# optoreflector.net
KiCad netlist of a schematic drawn in EAGLE
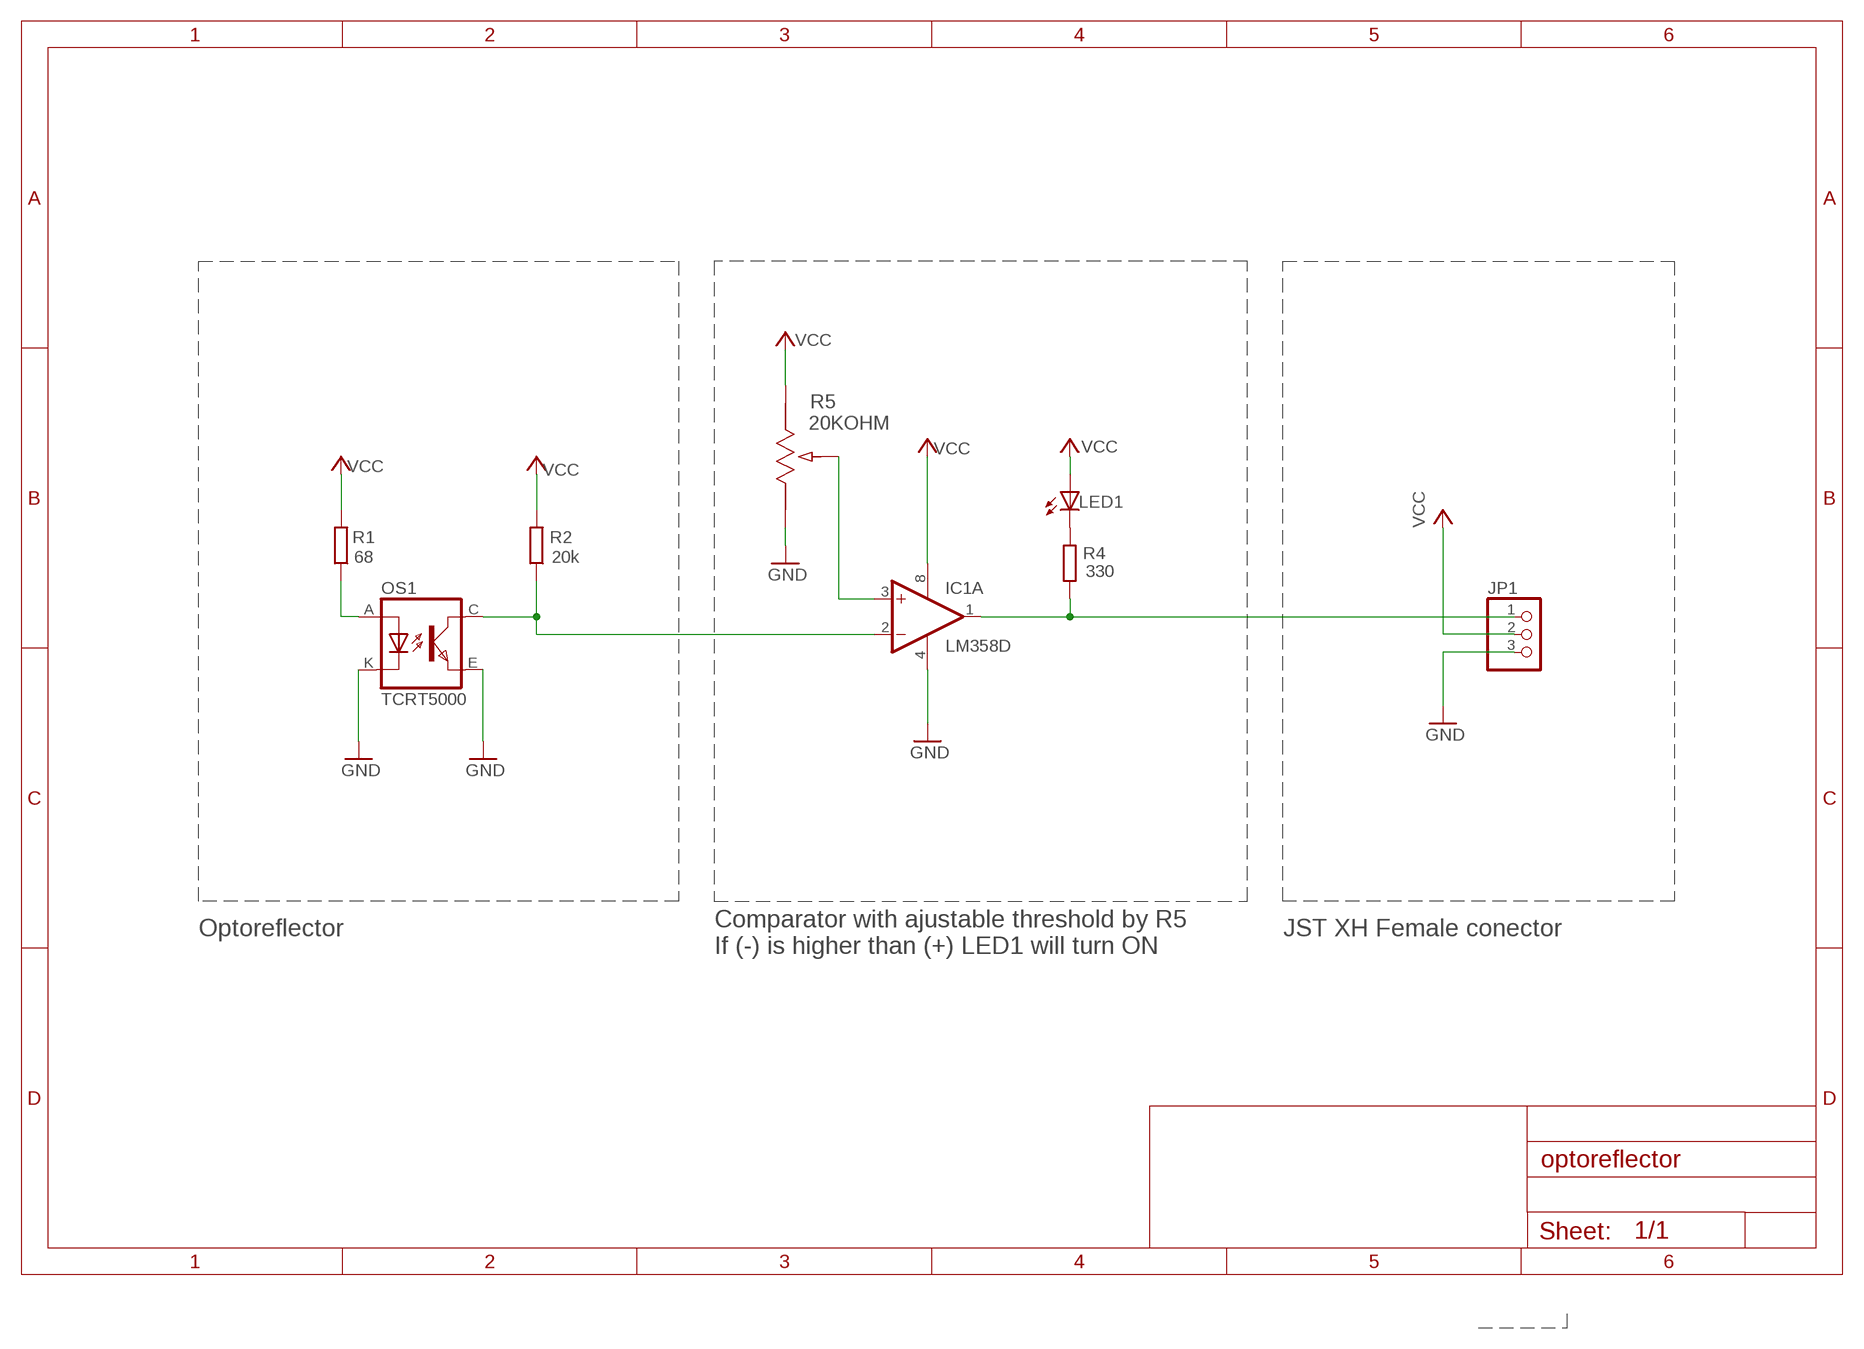
[diagram p0: schematic, sheet 1]

(export (version "E")
  (design (tool "Eeschema 10.0.6"))
  (components
    (comp (ref "IC1")
      (value "LM358D")
      (footprint "eagle-import:SO08")
      (libsource (lib "eagle-import") (part "LM358D"))
    )
    (comp (ref "JP1")
      (value "PINHD-1X3")
      (footprint "eagle-import:1X03")
      (libsource (lib "eagle-import") (part "PINHD-1X3"))
    )
    (comp (ref "LED1")
      (value "LEDCHIP-LED0805")
      (footprint "eagle-import:CHIP-LED0805")
      (libsource (lib "eagle-import") (part "LEDCHIP-LED0805"))
    )
    (comp (ref "OS1")
      (value "TCRT5000")
      (footprint "eagle-import:TCRT5000")
      (libsource (lib "eagle-import") (part "TCRT5000"))
    )
    (comp (ref "R1")
      (value "68")
      (footprint "eagle-import:R0805")
      (libsource (lib "eagle-import") (part "R-EU_R0805"))
    )
    (comp (ref "R2")
      (value "20k")
      (footprint "eagle-import:R0805")
      (libsource (lib "eagle-import") (part "R-EU_R0805"))
    )
    (comp (ref "R4")
      (value "330")
      (footprint "eagle-import:R0805")
      (libsource (lib "eagle-import") (part "R-EU_R0805"))
    )
    (comp (ref "R5")
      (value "20KOHM")
      (footprint "eagle-import:POT_EVM2W")
      (fields (field (name "MPN") "EVM2WSX80B24") (field (name "TOLERANCE") "±25 %"))
      (libsource (lib "eagle-import") (part "EVM-2W2WSX80B24"))
    )
  )
  (nets
    (net (code "1") (name "GND") (class "Default")
      (node (ref "IC1") (pin "4") (pinfunction "V-_4") (pintype "power_in"))
      (node (ref "JP1") (pin "3") (pinfunction "3_3") (pintype "passive"))
      (node (ref "OS1") (pin "E") (pinfunction "EMITTER_E") (pintype "passive"))
      (node (ref "OS1") (pin "K") (pinfunction "CATHODE_K") (pintype "passive"))
      (node (ref "R5") (pin "3") (pinfunction "3_3") (pintype "passive"))
    )
    (net (code "2") (name "Net-(IC1A-+IN)") (class "Default")
      (node (ref "IC1") (pin "3") (pinfunction "+IN_3") (pintype "input"))
      (node (ref "R5") (pin "2") (pinfunction "2_2") (pintype "passive"))
    )
    (net (code "3") (name "Net-(IC1A--IN)") (class "Default")
      (node (ref "IC1") (pin "2") (pinfunction "-IN_2") (pintype "input"))
      (node (ref "OS1") (pin "C") (pinfunction "COLLECTOR_C") (pintype "passive"))
      (node (ref "R2") (pin "1") (pinfunction "1_1") (pintype "passive"))
    )
    (net (code "4") (name "Net-(IC1A-OUT)") (class "Default")
      (node (ref "IC1") (pin "1") (pinfunction "OUT_1") (pintype "output"))
      (node (ref "JP1") (pin "1") (pinfunction "1_1") (pintype "passive"))
      (node (ref "R4") (pin "1") (pinfunction "1_1") (pintype "passive"))
    )
    (net (code "5") (name "Net-(LED1-PadC)") (class "Default")
      (node (ref "LED1") (pin "C") (pinfunction "C_C") (pintype "passive"))
      (node (ref "R4") (pin "2") (pinfunction "2_2") (pintype "passive"))
    )
    (net (code "6") (name "Net-(OS1-ANODE)") (class "Default")
      (node (ref "OS1") (pin "A") (pinfunction "ANODE_A") (pintype "passive"))
      (node (ref "R1") (pin "1") (pinfunction "1_1") (pintype "passive"))
    )
    (net (code "7") (name "VCC") (class "Default")
      (node (ref "IC1") (pin "8") (pinfunction "V+_8") (pintype "power_in"))
      (node (ref "JP1") (pin "2") (pinfunction "2_2") (pintype "passive"))
      (node (ref "LED1") (pin "A") (pinfunction "A_A") (pintype "passive"))
      (node (ref "R1") (pin "2") (pinfunction "2_2") (pintype "passive"))
      (node (ref "R2") (pin "2") (pinfunction "2_2") (pintype "passive"))
      (node (ref "R5") (pin "1") (pinfunction "1_1") (pintype "passive"))
    )
  )
)
